# NIXIE_Mainboard.net
KiCad netlist of a schematic drawn in Altium Designer
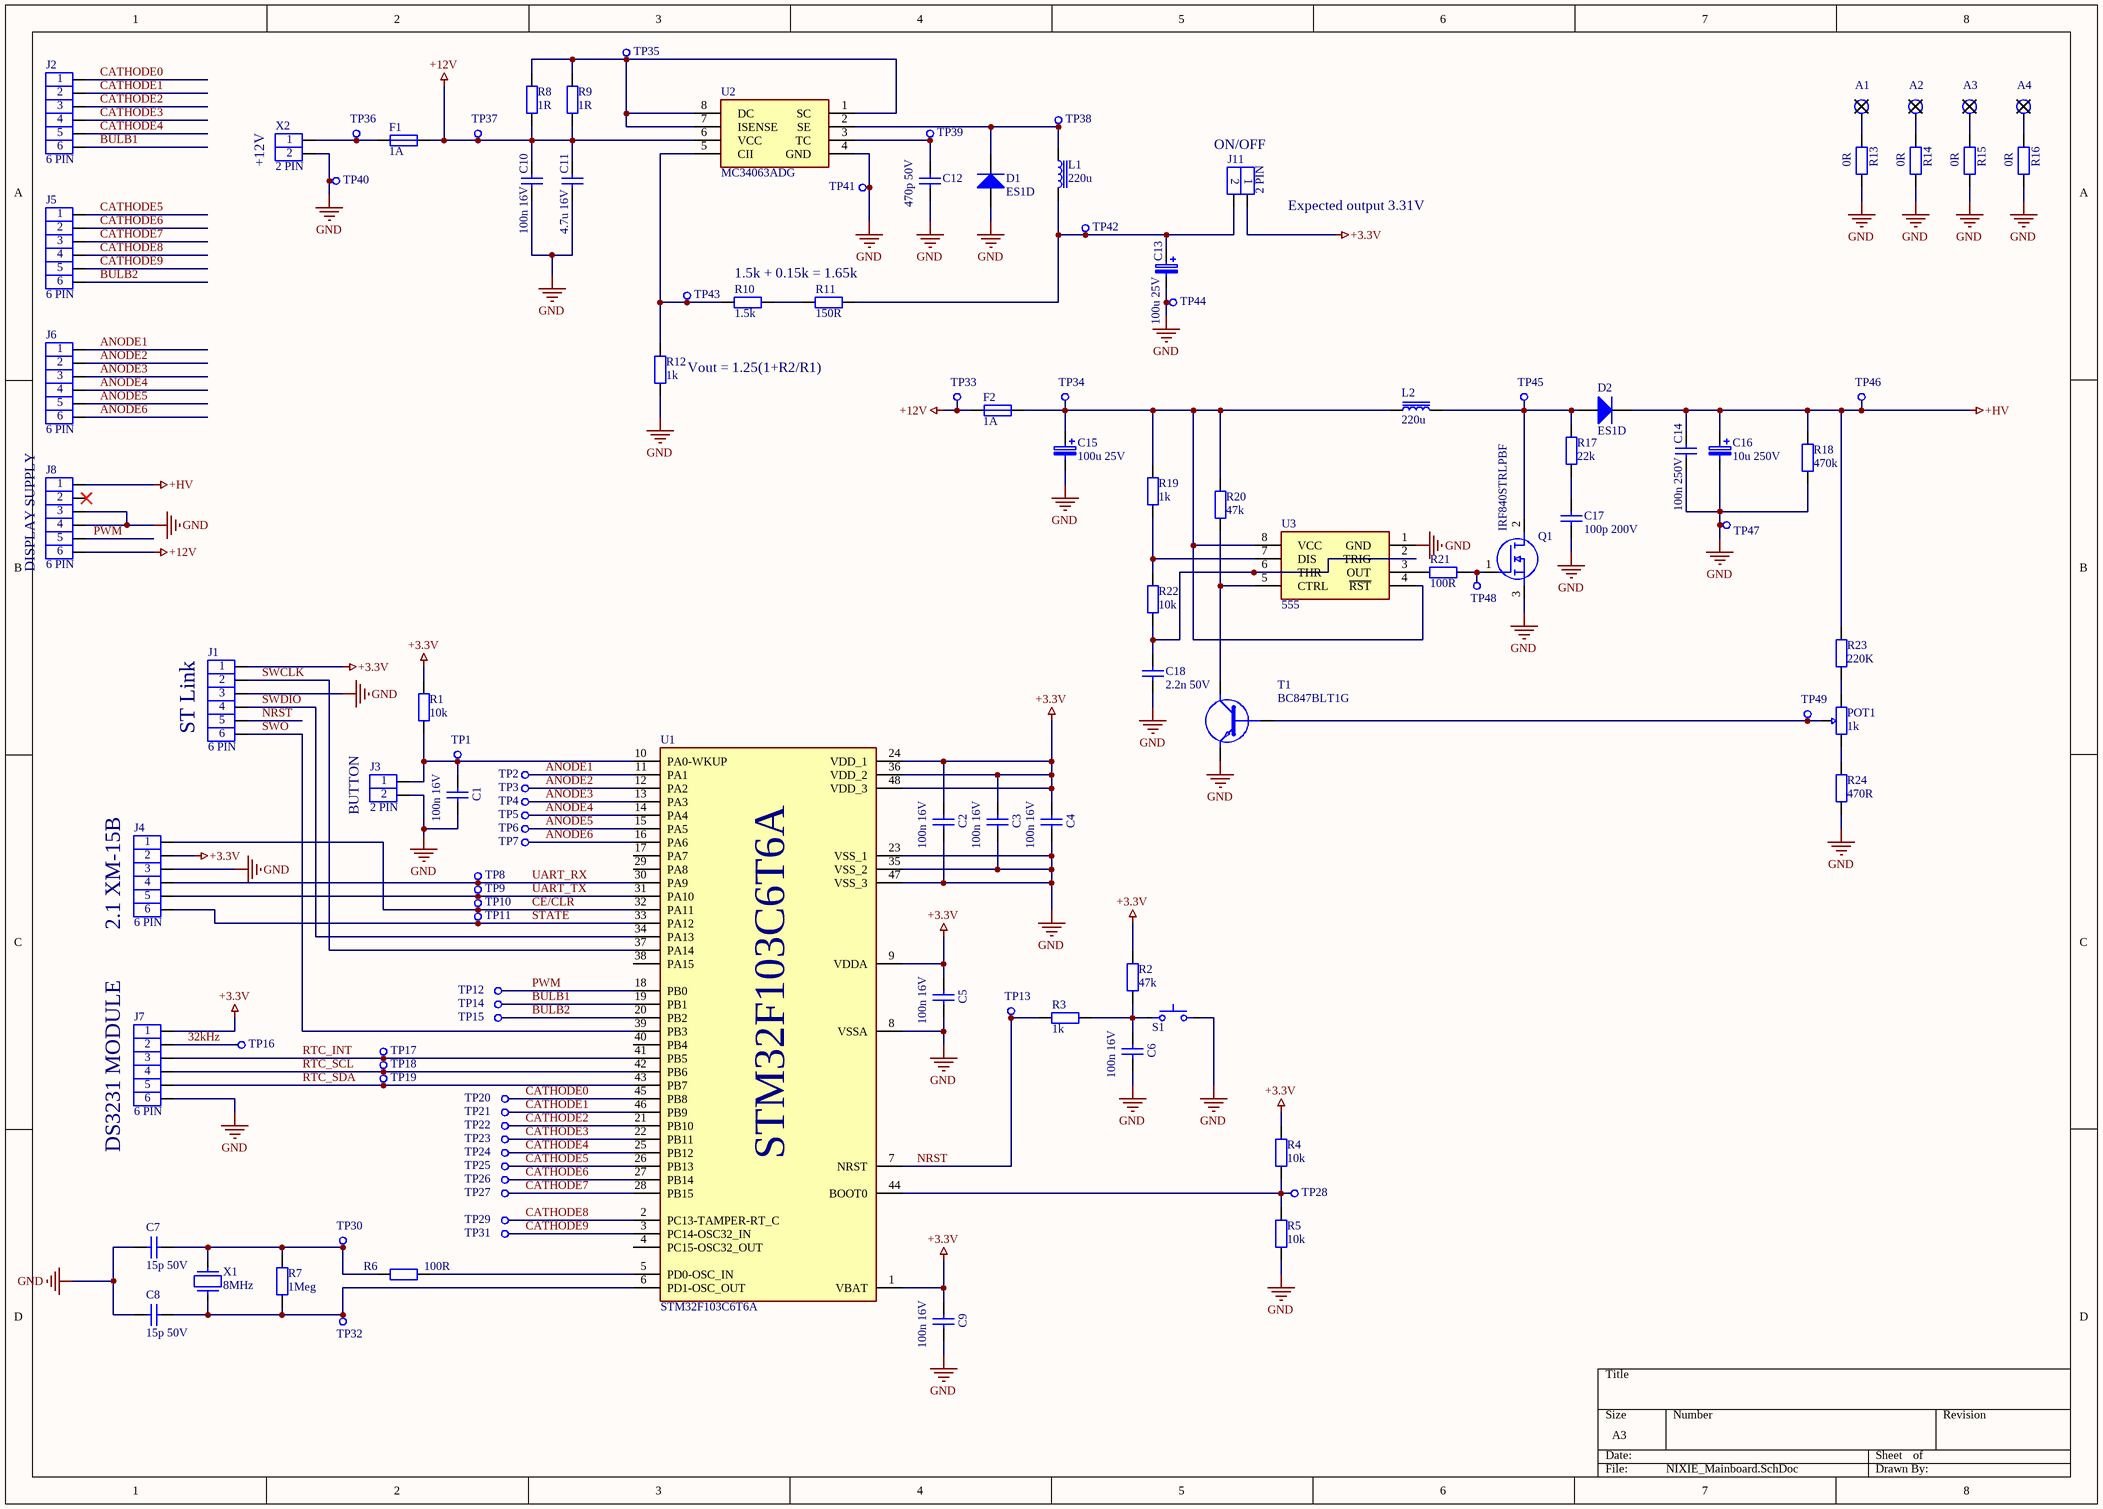
[diagram p0: NIXIE_Mainboard.SchDoc]

(export (version "E")
  (design (tool "Eeschema 10.0.6"))
  (components
    (comp (ref "A1")
      (value "3mm")
      (footprint "FOOTPRINTS:HOLE M3")
      (description "Mechanical M3 Hole")
      (libsource (lib "SYMBOLS") (part "Mechanical M3 Hole"))
    )
    (comp (ref "A2")
      (value "3mm")
      (footprint "FOOTPRINTS:HOLE M3")
      (description "Mechanical M3 Hole")
      (libsource (lib "SYMBOLS") (part "Mechanical M3 Hole"))
    )
    (comp (ref "A3")
      (value "3mm")
      (footprint "FOOTPRINTS:HOLE M3")
      (description "Mechanical M3 Hole")
      (libsource (lib "SYMBOLS") (part "Mechanical M3 Hole"))
    )
    (comp (ref "A4")
      (value "3mm")
      (footprint "FOOTPRINTS:HOLE M3")
      (description "Mechanical M3 Hole")
      (libsource (lib "SYMBOLS") (part "Mechanical M3 Hole"))
    )
    (comp (ref "C1")
      (value "100n 16V")
      (footprint "FOOTPRINTS:CAPACITOR 0603")
      (description "Multilayer Ceramic Capacitors MLCC - SMD/SMT 0603 16VDC 0.1uF 10% X7R")
      (fields
        (field (name "MANUFACTURER") "Taiyo Yuden")
        (field (name "MANUFACTURER PART NUMBER") "EMK107B7104KA-T")
      )
      (libsource (lib "SYMBOLS") (part "Capacitor 100n 16V 10% X7R 0603"))
    )
    (comp (ref "C2")
      (value "100n 16V")
      (footprint "FOOTPRINTS:CAPACITOR 0603")
      (description "Multilayer Ceramic Capacitors MLCC - SMD/SMT 0603 16VDC 0.1uF 10% X7R")
      (fields
        (field (name "MANUFACTURER") "Taiyo Yuden")
        (field (name "MANUFACTURER PART NUMBER") "EMK107B7104KA-T")
      )
      (libsource (lib "SYMBOLS") (part "Capacitor 100n 16V 10% X7R 0603"))
    )
    (comp (ref "C3")
      (value "100n 16V")
      (footprint "FOOTPRINTS:CAPACITOR 0603")
      (description "Multilayer Ceramic Capacitors MLCC - SMD/SMT 0603 16VDC 0.1uF 10% X7R")
      (fields
        (field (name "MANUFACTURER") "Taiyo Yuden")
        (field (name "MANUFACTURER PART NUMBER") "EMK107B7104KA-T")
      )
      (libsource (lib "SYMBOLS") (part "Capacitor 100n 16V 10% X7R 0603"))
    )
    (comp (ref "C4")
      (value "100n 16V")
      (footprint "FOOTPRINTS:CAPACITOR 0603")
      (description "Multilayer Ceramic Capacitors MLCC - SMD/SMT 0603 16VDC 0.1uF 10% X7R")
      (fields
        (field (name "MANUFACTURER") "Taiyo Yuden")
        (field (name "MANUFACTURER PART NUMBER") "EMK107B7104KA-T")
      )
      (libsource (lib "SYMBOLS") (part "Capacitor 100n 16V 10% X7R 0603"))
    )
    (comp (ref "C5")
      (value "100n 16V")
      (footprint "FOOTPRINTS:CAPACITOR 0603")
      (description "Multilayer Ceramic Capacitors MLCC - SMD/SMT 0603 16VDC 0.1uF 10% X7R")
      (fields
        (field (name "MANUFACTURER") "Taiyo Yuden")
        (field (name "MANUFACTURER PART NUMBER") "EMK107B7104KA-T")
      )
      (libsource (lib "SYMBOLS") (part "Capacitor 100n 16V 10% X7R 0603"))
    )
    (comp (ref "C6")
      (value "100n 16V")
      (footprint "FOOTPRINTS:CAPACITOR 0603")
      (description "Multilayer Ceramic Capacitors MLCC - SMD/SMT 0603 16VDC 0.1uF 10% X7R")
      (fields
        (field (name "MANUFACTURER") "Taiyo Yuden")
        (field (name "MANUFACTURER PART NUMBER") "EMK107B7104KA-T")
      )
      (libsource (lib "SYMBOLS") (part "Capacitor 100n 16V 10% X7R 0603"))
    )
    (comp (ref "C7")
      (value "15p 50V")
      (footprint "FOOTPRINTS:CAPACITOR 0603")
      (description "Multilayer Ceramic Capacitors MLCC - SMD/SMT 50 V 15 pF C0G 0603 5%")
      (fields
        (field (name "MANUFACTURER") "YAGEO")
        (field (name "MANUFACTURER PART NUMBER") "CC0603JPNPO9BN150")
      )
      (libsource (lib "SYMBOLS") (part "Capacitor 15p 50V 10% X7R 0603"))
    )
    (comp (ref "C8")
      (value "15p 50V")
      (footprint "FOOTPRINTS:CAPACITOR 0603")
      (description "Multilayer Ceramic Capacitors MLCC - SMD/SMT 50 V 15 pF C0G 0603 5%")
      (fields
        (field (name "MANUFACTURER") "YAGEO")
        (field (name "MANUFACTURER PART NUMBER") "CC0603JPNPO9BN150")
      )
      (libsource (lib "SYMBOLS") (part "Capacitor 15p 50V 10% X7R 0603"))
    )
    (comp (ref "C9")
      (value "100n 16V")
      (footprint "FOOTPRINTS:CAPACITOR 0603")
      (description "Multilayer Ceramic Capacitors MLCC - SMD/SMT 0603 16VDC 0.1uF 10% X7R")
      (fields
        (field (name "MANUFACTURER") "Taiyo Yuden")
        (field (name "MANUFACTURER PART NUMBER") "EMK107B7104KA-T")
      )
      (libsource (lib "SYMBOLS") (part "Capacitor 100n 16V 10% X7R 0603"))
    )
    (comp (ref "C10")
      (value "100n 16V")
      (footprint "FOOTPRINTS:CAPACITOR 0603")
      (description "Multilayer Ceramic Capacitors MLCC - SMD/SMT 0603 16VDC 0.1uF 10% X7R")
      (fields
        (field (name "MANUFACTURER") "Taiyo Yuden")
        (field (name "MANUFACTURER PART NUMBER") "EMK107B7104KA-T")
      )
      (libsource (lib "SYMBOLS") (part "Capacitor 100n 16V 10% X7R 0603"))
    )
    (comp (ref "C11")
      (value "4.7u 16V")
      (footprint "FOOTPRINTS:CAPACITOR 0805")
      (description "Multilayer Ceramic Capacitors MLCC - SMD/SMT 0805 16VDC 4.7uF 10% X7R")
      (fields
        (field (name "MANUFACTURER") "Taiyo Yuden")
        (field (name "MANUFACTURER PART NUMBER") "EMK212B7475KG-T")
      )
      (libsource (lib "SYMBOLS") (part "Capacitor 4.7u 16V 10% X7R 0805"))
    )
    (comp (ref "C12")
      (value "470p 50V")
      (footprint "FOOTPRINTS:CAPACITOR 0603")
      (description "Multilayer Ceramic Capacitors MLCC - SMD/SMT 470p +-10% 16VX7R")
      (fields
        (field (name "MANUFACTURER") "Walsin")
        (field (name "MANUFACTURER PART NUMBER") "CC0603KPX7R9BB471")
      )
      (libsource (lib "SYMBOLS") (part "Capacitor 470p 50V 10% X7R 0603"))
    )
    (comp (ref "C13")
      (value "100u 25V")
      (footprint "FOOTPRINTS:CAPACITOR 6.3X11MM THT")
      (description "Aluminum Electrolytic Capacitors - Radial Leaded 25V 100uF 105C 6.3x11mm")
      (fields
        (field (name "MANUFACTURER") "Lelon")
        (field (name "MANUFACTURER PART NUMBER") "RGA101M1EBK-0611G")
      )
      (libsource (lib "SYMBOLS") (part "Capacitor 100u 25V 20% Aluminum 6.3x11mm THT"))
    )
    (comp (ref "C14")
      (value "100n 250V")
      (footprint "FOOTPRINTS:CAPACITOR 1206")
      (description "Multilayer Ceramic Capacitors MLCC - SMD/SMT 250V 1000pF X7R 1206 5% Flex Term")
      (fields
        (field (name "MANUFACTURER") "KEMET")
        (field (name "MANUFACTURER PART NUMBER") "C1206X102JARACTU")
      )
      (libsource (lib "SYMBOLS") (part "Capacitor 100n 250V 5% X7R 1206"))
    )
    (comp (ref "C15")
      (value "100u 25V")
      (footprint "FOOTPRINTS:CAPACITOR 6.3X11MM THT")
      (description "Aluminum Electrolytic Capacitors - Radial Leaded 25V 100uF 105C 6.3x11mm")
      (fields
        (field (name "MANUFACTURER") "Lelon")
        (field (name "MANUFACTURER PART NUMBER") "RGA101M1EBK-0611G")
      )
      (libsource (lib "SYMBOLS") (part "Capacitor 100u 25V 20% Aluminum 6.3x11mm THT"))
    )
    (comp (ref "C16")
      (value "10u 250V")
      (footprint "FOOTPRINTS:CAPACITOR 10X20MM THT")
      (description "Aluminum Electrolytic Capacitors - Radial Leaded 25V 100uF 105C 6.3x11mm")
      (fields
        (field (name "MANUFACTURER") "Producent")
        (field (name "MANUFACTURER PART NUMBER") "PJ2E100MNN1020")
      )
      (libsource (lib "SYMBOLS") (part "Capacitor 10u 250V 20% Aluminum 10x20mm THT"))
    )
    (comp (ref "C17")
      (value "100p 200V")
      (footprint "FOOTPRINTS:CAPACITOR 1206")
      (description "Multilayer Ceramic Capacitors MLCC - SMD/SMT 200V 100pF X7R 1206 10% AEC-Q200")
      (fields
        (field (name "MANUFACTURER") "KEMET")
        (field (name "MANUFACTURER PART NUMBER") "C1206C101K2RACAUTO")
      )
      (libsource (lib "SYMBOLS") (part "Capacitor 100p 200V 10% X7R 1206"))
    )
    (comp (ref "C18")
      (value "2.2n 50V")
      (footprint "FOOTPRINTS:CAPACITOR 0603")
      (description "Multilayer Ceramic Capacitors MLCC - SMD/SMT 0603 50VDC 2200pF 10% X7R AEC-Q200")
      (fields
        (field (name "MANUFACTURER") "Taiyo Yuden")
        (field (name "MANUFACTURER PART NUMBER") "UMK107B7222KAHT")
      )
      (libsource (lib "SYMBOLS") (part "Capacitor 2.2n 50V 10% X7R 0603"))
    )
    (comp (ref "D1")
      (value "ES1D")
      (footprint "FOOTPRINTS:DIODE DO-214AC")
      (description "Rectifiers 1.0a Rectifier UF Recovery")
      (fields (field (name "MANUFACTURER") "onsemi / Fairchild"))
      (libsource (lib "SYMBOLS") (part "Diode 200V 1.5W 1A Rectifier Vf 920mV ES1D"))
    )
    (comp (ref "D2")
      (value "ES1D")
      (footprint "FOOTPRINTS:DIODE DO-214AC")
      (description "Rectifiers 1.0a Rectifier UF Recovery")
      (fields (field (name "MANUFACTURER") "onsemi / Fairchild"))
      (libsource (lib "SYMBOLS") (part "Diode 200V 1.5W 1A Rectifier Vf 920mV ES1D"))
    )
    (comp (ref "F1")
      (value "1A")
      (footprint "FOOTPRINTS:FUSE 1206")
      (description "Surface Mount Fuses 1A 63V TIME DELAY")
      (fields
        (field (name "MANUFACTURER") "Bourns")
        (field (name "MANUFACTURER PART NUMBER") "SF-1206HI100M-2")
      )
      (libsource (lib "SYMBOLS") (part "Fuse 1A 1% 1/4W 1206"))
    )
    (comp (ref "F2")
      (value "1A")
      (footprint "FOOTPRINTS:FUSE 1206")
      (description "Surface Mount Fuses 1A 63V TIME DELAY")
      (fields
        (field (name "MANUFACTURER") "Bourns")
        (field (name "MANUFACTURER PART NUMBER") "SF-1206HI100M-2")
      )
      (libsource (lib "SYMBOLS") (part "Fuse 1A 1% 1/4W 1206"))
    )
    (comp (ref "J1")
      (value "6 PIN")
      (footprint "FOOTPRINTS:MECHANICAL PINHEADER 6P 2.54MM MALE")
      (description "Headers & Wire Housings 2.54MM CGRIDIII HDR 6P VERT SR SEL AU")
      (fields (field (name "MANUFACTURER") "Molex") (field (name "MANUFACTURER PART NUMBER") "90120-0766"))
      (libsource (lib "SYMBOLS") (part "Mechanical Pinheader Male 6pin P=2.54mm THT"))
    )
    (comp (ref "J2")
      (value "6 PIN")
      (footprint "FOOTPRINTS:MECHANICAL PINHEADER 6P 2.54MM MALE")
      (description "Headers & Wire Housings 2.54MM CGRIDIII HDR 6P VERT SR SEL AU")
      (fields (field (name "MANUFACTURER") "Molex") (field (name "MANUFACTURER PART NUMBER") "90120-0766"))
      (libsource (lib "SYMBOLS") (part "Mechanical Pinheader Male 6pin P=2.54mm THT"))
    )
    (comp (ref "J3")
      (value "2 PIN")
      (footprint "FOOTPRINTS:MECHANICAL PINHEADER 2P 2.54MM MALE")
      (description "Headers & Wire Housings 2.54MM CGRIDIII HDR 2P VERT SR SEL AU")
      (fields (field (name "MANUFACTURER") "Molex") (field (name "MANUFACTURER PART NUMBER") "90120-0762"))
      (libsource (lib "") (part "Mechanical Pinheader Male 2pin P=2.54mm THT_1"))
    )
    (comp (ref "J4")
      (value "6 PIN")
      (footprint "FOOTPRINTS:MECHANICAL PINHEADER 6P 2.54MM MALE")
      (description "Headers & Wire Housings 2.54MM CGRIDIII HDR 6P VERT SR SEL AU")
      (fields (field (name "MANUFACTURER") "Molex") (field (name "MANUFACTURER PART NUMBER") "90120-0766"))
      (libsource (lib "SYMBOLS") (part "Mechanical Pinheader Male 6pin P=2.54mm THT"))
    )
    (comp (ref "J5")
      (value "6 PIN")
      (footprint "FOOTPRINTS:MECHANICAL PINHEADER 6P 2.54MM MALE")
      (description "Headers & Wire Housings 2.54MM CGRIDIII HDR 6P VERT SR SEL AU")
      (fields (field (name "MANUFACTURER") "Molex") (field (name "MANUFACTURER PART NUMBER") "90120-0766"))
      (libsource (lib "SYMBOLS") (part "Mechanical Pinheader Male 6pin P=2.54mm THT"))
    )
    (comp (ref "J6")
      (value "6 PIN")
      (footprint "FOOTPRINTS:MECHANICAL PINHEADER 6P 2.54MM MALE")
      (description "Headers & Wire Housings 2.54MM CGRIDIII HDR 6P VERT SR SEL AU")
      (fields (field (name "MANUFACTURER") "Molex") (field (name "MANUFACTURER PART NUMBER") "90120-0766"))
      (libsource (lib "SYMBOLS") (part "Mechanical Pinheader Male 6pin P=2.54mm THT"))
    )
    (comp (ref "J7")
      (value "6 PIN")
      (footprint "FOOTPRINTS:MECHANICAL PINHEADER 6P 2.54MM MALE")
      (description "Headers & Wire Housings 2.54MM CGRIDIII HDR 6P VERT SR SEL AU")
      (fields (field (name "MANUFACTURER") "Molex") (field (name "MANUFACTURER PART NUMBER") "90120-0766"))
      (libsource (lib "SYMBOLS") (part "Mechanical Pinheader Male 6pin P=2.54mm THT"))
    )
    (comp (ref "J8")
      (value "6 PIN")
      (footprint "FOOTPRINTS:MECHANICAL PINHEADER 6P 2.54MM MALE")
      (description "Headers & Wire Housings 2.54MM CGRIDIII HDR 6P VERT SR SEL AU")
      (fields (field (name "MANUFACTURER") "Molex") (field (name "MANUFACTURER PART NUMBER") "90120-0766"))
      (libsource (lib "SYMBOLS") (part "Mechanical Pinheader Male 6pin P=2.54mm THT"))
    )
    (comp (ref "J11")
      (value "2 PIN")
      (footprint "FOOTPRINTS:MECHANICAL PINHEADER 2P 2.54MM MALE")
      (description "Headers & Wire Housings 2.54MM CGRIDIII HDR 2P VERT SR SEL AU")
      (fields (field (name "MANUFACTURER") "Molex") (field (name "MANUFACTURER PART NUMBER") "90120-0762"))
      (libsource (lib "SYMBOLS") (part "Mechanical Pinheader Male 2pin P=2.54mm THT"))
    )
    (comp (ref "L1")
      (value "220u")
      (footprint "FOOTPRINTS:INDUCTOR CDRH127")
      (description "Power Inductors - SMD 220uH 0.95A Dual wind inductor")
      (fields
        (field (name "MANUFACTURER") "Murata Power Solutions")
        (field (name "MANUFACTURER PART NUMBER") "49221C")
      )
      (libsource (lib "SYMBOLS") (part "Inductor 220uH 0.95A Shielded 49221C"))
    )
    (comp (ref "L2")
      (value "220u")
      (footprint "FOOTPRINTS:INDUCTOR CDRH127")
      (description "Power Inductors - SMD 220uH 0.95A Dual wind inductor")
      (fields
        (field (name "MANUFACTURER") "Murata Power Solutions")
        (field (name "MANUFACTURER PART NUMBER") "49221C")
      )
      (libsource (lib "") (part "Inductor 220uH 0.95A Shielded 49221C_1"))
    )
    (comp (ref "POT1")
      (value "1k")
      (footprint "FOOTPRINTS:POTENTIOMETER TC33X")
      (description "Trimmer Resistors - SMD TRIMMER-3MM OPEN FRAME")
      (fields (field (name "MANUFACTURER") "Bourns") (field (name "MANUFACTURER PART NUMBER") "TC33X-1-102E"))
      (libsource (lib "SYMBOLS") (part "Potentiometer PCB 1k SMD TC33X-1-102E"))
    )
    (comp (ref "Q1")
      (value "IRF840STRLPBF")
      (footprint "FOOTPRINTS:TO-263-3")
      (description "MOSFET 500V N-CH HEXFET D2-PA")
      (fields (field (name "MANUFACTURER") "Vishay Semiconductors"))
      (libsource (lib "SYMBOLS") (part "Transistor N-MOSFET 500V 8A TO-263-3 IRF840STRLPBF"))
    )
    (comp (ref "R1")
      (value "10k")
      (footprint "FOOTPRINTS:RESISTOR 0603")
      (description "Thin Film Resistors - SMD 1/10W 10K ohm 1% 50ppm")
      (fields
        (field (name "MANUFACTURER") "Yageo")
        (field (name "MANUFACTURER PART NUMBER") "RT0603FRE1310KL")
      )
      (libsource (lib "SYMBOLS") (part "Resistor 10k 1% 1/10W 0603"))
    )
    (comp (ref "R2")
      (value "47k")
      (footprint "FOOTPRINTS:RESISTOR 0603")
      (description "Thin Film Resistors - SMD 1/10W 47K ohm 1% 50ppm")
      (fields
        (field (name "MANUFACTURER") "Yageo")
        (field (name "MANUFACTURER PART NUMBER") "RT0603FRE1347KL")
      )
      (libsource (lib "SYMBOLS") (part "Resistor 47k 1% 1/10W 0603"))
    )
    (comp (ref "R3")
      (value "1k")
      (footprint "FOOTPRINTS:RESISTOR 0603")
      (description "Thin Film Resistors - SMD 1/10W 1K ohm 1% 50ppm")
      (fields
        (field (name "MANUFACTURER") "Yageo")
        (field (name "MANUFACTURER PART NUMBER") "RT0603FRE071KL")
      )
      (libsource (lib "SYMBOLS") (part "Resistor 1k 1% 1/10W 0603"))
    )
    (comp (ref "R4")
      (value "10k")
      (footprint "FOOTPRINTS:RESISTOR 0603")
      (description "Thin Film Resistors - SMD 1/10W 10K ohm 1% 50ppm")
      (fields
        (field (name "MANUFACTURER") "Yageo")
        (field (name "MANUFACTURER PART NUMBER") "RT0603FRE1310KL")
      )
      (libsource (lib "SYMBOLS") (part "Resistor 10k 1% 1/10W 0603"))
    )
    (comp (ref "R5")
      (value "10k")
      (footprint "FOOTPRINTS:RESISTOR 0603")
      (description "Thin Film Resistors - SMD 1/10W 10K ohm 1% 50ppm")
      (fields
        (field (name "MANUFACTURER") "Yageo")
        (field (name "MANUFACTURER PART NUMBER") "RT0603FRE1310KL")
      )
      (libsource (lib "SYMBOLS") (part "Resistor 10k 1% 1/10W 0603"))
    )
    (comp (ref "R6")
      (value "100R")
      (footprint "FOOTPRINTS:RESISTOR 0603")
      (description "Thin Film Resistors - SMD 1/10W 100R ohm 1% 50ppm")
      (fields
        (field (name "MANUFACTURER") "Yageo")
        (field (name "MANUFACTURER PART NUMBER") "RT0603FRE07100RL")
      )
      (libsource (lib "SYMBOLS") (part "Resistor 100R 1% 1/10W 0603"))
    )
    (comp (ref "R7")
      (value "1Meg")
      (footprint "FOOTPRINTS:RESISTOR 0603")
      (description "Thin Film Resistors - SMD 1/10W 1M ohm 1% 50ppm")
      (fields
        (field (name "MANUFACTURER") "Yageo")
        (field (name "MANUFACTURER PART NUMBER") "RT0603FRE071ML")
      )
      (libsource (lib "SYMBOLS") (part "Resistor 1Meg 1% 1/10W 0603"))
    )
    (comp (ref "R8")
      (value "1R")
      (footprint "FOOTPRINTS:RESISTOR 1206")
      (description "Thick Film Resistors - SMD 1 Ohms 250 mW 1206 1%")
      (fields
        (field (name "MANUFACTURER") "Yageo")
        (field (name "MANUFACTURER PART NUMBER") "RC1206FR-071RL")
      )
      (libsource (lib "SYMBOLS") (part "Resistor 1R 1% 1/4W 1206"))
    )
    (comp (ref "R9")
      (value "1R")
      (footprint "FOOTPRINTS:RESISTOR 1206")
      (description "Thick Film Resistors - SMD 1 Ohms 250 mW 1206 1%")
      (fields
        (field (name "MANUFACTURER") "Yageo")
        (field (name "MANUFACTURER PART NUMBER") "RC1206FR-071RL")
      )
      (libsource (lib "SYMBOLS") (part "Resistor 1R 1% 1/4W 1206"))
    )
    (comp (ref "R10")
      (value "1.5k")
      (footprint "FOOTPRINTS:RESISTOR 0603")
      (description "Thin Film Resistors - SMD 1/10W 1.5K ohm 1% 50ppm")
      (fields
        (field (name "MANUFACTURER") "Yageo")
        (field (name "MANUFACTURER PART NUMBER") "RT0603FRE071K5L")
      )
      (libsource (lib "SYMBOLS") (part "Resistor 1.5k 1% 1/10W 0603"))
    )
    (comp (ref "R11")
      (value "150R")
      (footprint "FOOTPRINTS:RESISTOR 0603")
      (description "Thin Film Resistors - SMD 1/10W 150R ohm 1% 50ppm")
      (fields
        (field (name "MANUFACTURER") "Yageo")
        (field (name "MANUFACTURER PART NUMBER") "RT0603FRE07150RL")
      )
      (libsource (lib "SYMBOLS") (part "Resistor 150R 1% 1/10W 0603"))
    )
    (comp (ref "R12")
      (value "1k")
      (footprint "FOOTPRINTS:RESISTOR 0603")
      (description "Thin Film Resistors - SMD 1/10W 1K ohm 1% 50ppm")
      (fields
        (field (name "MANUFACTURER") "Yageo")
        (field (name "MANUFACTURER PART NUMBER") "RT0603FRE071KL")
      )
      (libsource (lib "") (part "Resistor 1k 1% 1/10W 0603_1"))
    )
    (comp (ref "R13")
      (value "0R")
      (footprint "FOOTPRINTS:RESISTOR 0603")
      (description "Thick Film Resistors - SMD 0 Ohms 100 mW 0603 5%")
      (fields
        (field (name "MANUFACTURER") "Yageo")
        (field (name "MANUFACTURER PART NUMBER") "RC0603JR-070RL")
      )
      (libsource (lib "SYMBOLS") (part "Resistor 0R 1% 1/10W 0603"))
    )
    (comp (ref "R14")
      (value "0R")
      (footprint "FOOTPRINTS:RESISTOR 0603")
      (description "Thick Film Resistors - SMD 0 Ohms 100 mW 0603 5%")
      (fields
        (field (name "MANUFACTURER") "Yageo")
        (field (name "MANUFACTURER PART NUMBER") "RC0603JR-070RL")
      )
      (libsource (lib "SYMBOLS") (part "Resistor 0R 1% 1/10W 0603"))
    )
    (comp (ref "R15")
      (value "0R")
      (footprint "FOOTPRINTS:RESISTOR 0603")
      (description "Thick Film Resistors - SMD 0 Ohms 100 mW 0603 5%")
      (fields
        (field (name "MANUFACTURER") "Yageo")
        (field (name "MANUFACTURER PART NUMBER") "RC0603JR-070RL")
      )
      (libsource (lib "SYMBOLS") (part "Resistor 0R 1% 1/10W 0603"))
    )
    (comp (ref "R16")
      (value "0R")
      (footprint "FOOTPRINTS:RESISTOR 0603")
      (description "Thick Film Resistors - SMD 0 Ohms 100 mW 0603 5%")
      (fields
        (field (name "MANUFACTURER") "Yageo")
        (field (name "MANUFACTURER PART NUMBER") "RC0603JR-070RL")
      )
      (libsource (lib "SYMBOLS") (part "Resistor 0R 1% 1/10W 0603"))
    )
    (comp (ref "R17")
      (value "22k")
      (footprint "FOOTPRINTS:RESISTOR 1206")
      (description "Thin Film Resistors - SMD 1/4W 22 kohm 1% 50ppm")
      (fields
        (field (name "MANUFACTURER") "Yageo")
        (field (name "MANUFACTURER PART NUMBER") "RT1206FRE0722KL")
      )
      (libsource (lib "SYMBOLS") (part "Resistor 22k 1% 1/4W 1206"))
    )
    (comp (ref "R18")
      (value "470k")
      (footprint "FOOTPRINTS:RESISTOR 1206")
      (description "Thin Film Resistors - SMD 1/4W470 kohm 1% 50ppm")
      (fields
        (field (name "MANUFACTURER") "Yageo")
        (field (name "MANUFACTURER PART NUMBER") "RT1206FRE07470KL")
      )
      (libsource (lib "SYMBOLS") (part "Resistor 470k 1% 1/4W 1206"))
    )
    (comp (ref "R19")
      (value "1k")
      (footprint "FOOTPRINTS:RESISTOR 0603")
      (description "Thin Film Resistors - SMD 1/10W 1K ohm 1% 50ppm")
      (fields
        (field (name "MANUFACTURER") "Yageo")
        (field (name "MANUFACTURER PART NUMBER") "RT0603FRE071KL")
      )
      (libsource (lib "") (part "Resistor 1k 1% 1/10W 0603_1"))
    )
    (comp (ref "R20")
      (value "47k")
      (footprint "FOOTPRINTS:RESISTOR 0603")
      (description "Thin Film Resistors - SMD 1/10W 47K ohm 1% 50ppm")
      (fields
        (field (name "MANUFACTURER") "Yageo")
        (field (name "MANUFACTURER PART NUMBER") "RT0603FRE1347KL")
      )
      (libsource (lib "SYMBOLS") (part "Resistor 47k 1% 1/10W 0603"))
    )
    (comp (ref "R21")
      (value "100R")
      (footprint "FOOTPRINTS:RESISTOR 0603")
      (description "Thin Film Resistors - SMD 1/10W 100R ohm 1% 50ppm")
      (fields
        (field (name "MANUFACTURER") "Yageo")
        (field (name "MANUFACTURER PART NUMBER") "RT0603FRE07100RL")
      )
      (libsource (lib "SYMBOLS") (part "Resistor 100R 1% 1/10W 0603"))
    )
    (comp (ref "R22")
      (value "10k")
      (footprint "FOOTPRINTS:RESISTOR 0603")
      (description "Thin Film Resistors - SMD 1/10W 10K ohm 1% 50ppm")
      (fields
        (field (name "MANUFACTURER") "Yageo")
        (field (name "MANUFACTURER PART NUMBER") "RT0603FRE1310KL")
      )
      (libsource (lib "SYMBOLS") (part "Resistor 10k 1% 1/10W 0603"))
    )
    (comp (ref "R23")
      (value "220K")
      (footprint "FOOTPRINTS:RESISTOR 1206")
      (description "Thin Film Resistors - SMD 1/4W 220 kohm 1% 50ppm")
      (fields
        (field (name "MANUFACTURER") "Yageo")
        (field (name "MANUFACTURER PART NUMBER") "RT1206FRE07220KL")
      )
      (libsource (lib "SYMBOLS") (part "Resistor 220k 1% 1/4W 1206"))
    )
    (comp (ref "R24")
      (value "470R")
      (footprint "FOOTPRINTS:RESISTOR 0603")
      (description "Thin Film Resistors - SMD 1/10W 470R ohm 1% 50ppm")
      (fields
        (field (name "MANUFACTURER") "Yageo")
        (field (name "MANUFACTURER PART NUMBER") "RT0603FRE07470RL")
      )
      (libsource (lib "SYMBOLS") (part "Resistor 470R 1% 1/10W 0603"))
    )
    (comp (ref "S1")
      (value "6x6mm")
      (footprint "FOOTPRINTS:MECHANICAL TACTSWITCH SMD 6x6")
      (description "Tactile Switches 6 x 6 mm, 5 mm Act Height, 260 gf, Black, Short Crimped, Through Hole, SPST")
      (fields
        (field (name "MANUFACTURER") "CUI Devices")
        (field (name "MANUFACTURER PART NUMBER") "TS02-66-50-BK-260-SCR-D")
      )
      (libsource (lib "SYMBOLS") (part "Mechanical Tact Switch 6x6mm THT"))
    )
    (comp (ref "T1")
      (value "BC847BLT1G")
      (footprint "FOOTPRINTS:SOT23-3")
      (description "Bipolar Transistors - BJT 100mA 50V NPN")
      (fields (field (name "MANUFACTURER") "onsemi"))
      (libsource (lib "SYMBOLS") (part "Transistor NPN 100mA 50V BC847BLT1G"))
    )
    (comp (ref "TP1")
      (value "1mm")
      (footprint "FOOTPRINTS:TEST POINT 1MM")
      (description "Tesp Point 1mm")
      (libsource (lib "SYMBOLS") (part "Mechanical Test Point 1mm"))
    )
    (comp (ref "TP2")
      (value "1mm")
      (footprint "FOOTPRINTS:TEST POINT 1MM")
      (description "Tesp Point 1mm")
      (libsource (lib "SYMBOLS") (part "Mechanical Test Point 1mm"))
    )
    (comp (ref "TP3")
      (value "1mm")
      (footprint "FOOTPRINTS:TEST POINT 1MM")
      (description "Tesp Point 1mm")
      (libsource (lib "SYMBOLS") (part "Mechanical Test Point 1mm"))
    )
    (comp (ref "TP4")
      (value "1mm")
      (footprint "FOOTPRINTS:TEST POINT 1MM")
      (description "Tesp Point 1mm")
      (libsource (lib "SYMBOLS") (part "Mechanical Test Point 1mm"))
    )
    (comp (ref "TP5")
      (value "1mm")
      (footprint "FOOTPRINTS:TEST POINT 1MM")
      (description "Tesp Point 1mm")
      (libsource (lib "SYMBOLS") (part "Mechanical Test Point 1mm"))
    )
    (comp (ref "TP6")
      (value "1mm")
      (footprint "FOOTPRINTS:TEST POINT 1MM")
      (description "Tesp Point 1mm")
      (libsource (lib "SYMBOLS") (part "Mechanical Test Point 1mm"))
    )
    (comp (ref "TP7")
      (value "1mm")
      (footprint "FOOTPRINTS:TEST POINT 1MM")
      (description "Tesp Point 1mm")
      (libsource (lib "SYMBOLS") (part "Mechanical Test Point 1mm"))
    )
    (comp (ref "TP8")
      (value "1mm")
      (footprint "FOOTPRINTS:TEST POINT 1MM")
      (description "Tesp Point 1mm")
      (libsource (lib "SYMBOLS") (part "Mechanical Test Point 1mm"))
    )
    (comp (ref "TP9")
      (value "1mm")
      (footprint "FOOTPRINTS:TEST POINT 1MM")
      (description "Tesp Point 1mm")
      (libsource (lib "SYMBOLS") (part "Mechanical Test Point 1mm"))
    )
    (comp (ref "TP10")
      (value "1mm")
      (footprint "FOOTPRINTS:TEST POINT 1MM")
      (description "Tesp Point 1mm")
      (libsource (lib "SYMBOLS") (part "Mechanical Test Point 1mm"))
    )
    (comp (ref "TP11")
      (value "1mm")
      (footprint "FOOTPRINTS:TEST POINT 1MM")
      (description "Tesp Point 1mm")
      (libsource (lib "SYMBOLS") (part "Mechanical Test Point 1mm"))
    )
    (comp (ref "TP12")
      (value "1mm")
      (footprint "FOOTPRINTS:TEST POINT 1MM")
      (description "Tesp Point 1mm")
      (libsource (lib "SYMBOLS") (part "Mechanical Test Point 1mm"))
    )
    (comp (ref "TP13")
      (value "1mm")
      (footprint "FOOTPRINTS:TEST POINT 1MM")
      (description "Tesp Point 1mm")
      (libsource (lib "SYMBOLS") (part "Mechanical Test Point 1mm"))
    )
    (comp (ref "TP14")
      (value "1mm")
      (footprint "FOOTPRINTS:TEST POINT 1MM")
      (description "Tesp Point 1mm")
      (libsource (lib "SYMBOLS") (part "Mechanical Test Point 1mm"))
    )
    (comp (ref "TP15")
      (value "1mm")
      (footprint "FOOTPRINTS:TEST POINT 1MM")
      (description "Tesp Point 1mm")
      (libsource (lib "SYMBOLS") (part "Mechanical Test Point 1mm"))
    )
    (comp (ref "TP16")
      (value "1mm")
      (footprint "FOOTPRINTS:TEST POINT 1MM")
      (description "Tesp Point 1mm")
      (libsource (lib "SYMBOLS") (part "Mechanical Test Point 1mm"))
    )
    (comp (ref "TP17")
      (value "1mm")
      (footprint "FOOTPRINTS:TEST POINT 1MM")
      (description "Tesp Point 1mm")
      (libsource (lib "SYMBOLS") (part "Mechanical Test Point 1mm"))
    )
    (comp (ref "TP18")
      (value "1mm")
      (footprint "FOOTPRINTS:TEST POINT 1MM")
      (description "Tesp Point 1mm")
      (libsource (lib "SYMBOLS") (part "Mechanical Test Point 1mm"))
    )
    (comp (ref "TP19")
      (value "1mm")
      (footprint "FOOTPRINTS:TEST POINT 1MM")
      (description "Tesp Point 1mm")
      (libsource (lib "SYMBOLS") (part "Mechanical Test Point 1mm"))
    )
    (comp (ref "TP20")
      (value "1mm")
      (footprint "FOOTPRINTS:TEST POINT 1MM")
      (description "Tesp Point 1mm")
      (libsource (lib "SYMBOLS") (part "Mechanical Test Point 1mm"))
    )
    (comp (ref "TP21")
      (value "1mm")
      (footprint "FOOTPRINTS:TEST POINT 1MM")
      (description "Tesp Point 1mm")
      (libsource (lib "SYMBOLS") (part "Mechanical Test Point 1mm"))
    )
    (comp (ref "TP22")
      (value "1mm")
      (footprint "FOOTPRINTS:TEST POINT 1MM")
      (description "Tesp Point 1mm")
      (libsource (lib "SYMBOLS") (part "Mechanical Test Point 1mm"))
    )
    (comp (ref "TP23")
      (value "1mm")
      (footprint "FOOTPRINTS:TEST POINT 1MM")
      (description "Tesp Point 1mm")
      (libsource (lib "SYMBOLS") (part "Mechanical Test Point 1mm"))
    )
    (comp (ref "TP24")
      (value "1mm")
      (footprint "FOOTPRINTS:TEST POINT 1MM")
      (description "Tesp Point 1mm")
      (libsource (lib "SYMBOLS") (part "Mechanical Test Point 1mm"))
    )
    (comp (ref "TP25")
      (value "1mm")
      (footprint "FOOTPRINTS:TEST POINT 1MM")
      (description "Tesp Point 1mm")
      (libsource (lib "SYMBOLS") (part "Mechanical Test Point 1mm"))
    )
    (comp (ref "TP26")
      (value "1mm")
      (footprint "FOOTPRINTS:TEST POINT 1MM")
      (description "Tesp Point 1mm")
      (libsource (lib "SYMBOLS") (part "Mechanical Test Point 1mm"))
    )
    (comp (ref "TP27")
      (value "1mm")
      (footprint "FOOTPRINTS:TEST POINT 1MM")
      (description "Tesp Point 1mm")
      (libsource (lib "SYMBOLS") (part "Mechanical Test Point 1mm"))
    )
    (comp (ref "TP28")
      (value "1mm")
      (footprint "FOOTPRINTS:TEST POINT 1MM")
      (description "Tesp Point 1mm")
      (libsource (lib "SYMBOLS") (part "Mechanical Test Point 1mm"))
    )
    (comp (ref "TP29")
      (value "1mm")
      (footprint "FOOTPRINTS:TEST POINT 1MM")
      (description "Tesp Point 1mm")
      (libsource (lib "SYMBOLS") (part "Mechanical Test Point 1mm"))
    )
    (comp (ref "TP30")
      (value "1mm")
      (footprint "FOOTPRINTS:TEST POINT 1MM")
      (description "Tesp Point 1mm")
      (libsource (lib "SYMBOLS") (part "Mechanical Test Point 1mm"))
    )
    (comp (ref "TP31")
      (value "1mm")
      (footprint "FOOTPRINTS:TEST POINT 1MM")
      (description "Tesp Point 1mm")
      (libsource (lib "SYMBOLS") (part "Mechanical Test Point 1mm"))
    )
    (comp (ref "TP32")
      (value "1mm")
      (footprint "FOOTPRINTS:TEST POINT 1MM")
      (description "Tesp Point 1mm")
      (libsource (lib "SYMBOLS") (part "Mechanical Test Point 1mm"))
    )
    (comp (ref "TP33")
      (value "1mm")
      (footprint "FOOTPRINTS:TEST POINT 1MM")
      (description "Tesp Point 1mm")
      (libsource (lib "SYMBOLS") (part "Mechanical Test Point 1mm"))
    )
    (comp (ref "TP34")
      (value "1mm")
      (footprint "FOOTPRINTS:TEST POINT 1MM")
      (description "Tesp Point 1mm")
      (libsource (lib "SYMBOLS") (part "Mechanical Test Point 1mm"))
    )
    (comp (ref "TP35")
      (value "1mm")
      (footprint "FOOTPRINTS:TEST POINT 1MM")
      (description "Tesp Point 1mm")
      (libsource (lib "SYMBOLS") (part "Mechanical Test Point 1mm"))
    )
    (comp (ref "TP36")
      (value "1mm")
      (footprint "FOOTPRINTS:TEST POINT 1MM")
      (description "Tesp Point 1mm")
      (libsource (lib "SYMBOLS") (part "Mechanical Test Point 1mm"))
    )
    (comp (ref "TP37")
      (value "1mm")
      (footprint "FOOTPRINTS:TEST POINT 1MM")
      (description "Tesp Point 1mm")
      (libsource (lib "SYMBOLS") (part "Mechanical Test Point 1mm"))
    )
    (comp (ref "TP38")
      (value "1mm")
      (footprint "FOOTPRINTS:TEST POINT 1MM")
      (description "Tesp Point 1mm")
      (libsource (lib "SYMBOLS") (part "Mechanical Test Point 1mm"))
    )
    (comp (ref "TP39")
      (value "1mm")
      (footprint "FOOTPRINTS:TEST POINT 1MM")
      (description "Tesp Point 1mm")
      (libsource (lib "SYMBOLS") (part "Mechanical Test Point 1mm"))
    )
    (comp (ref "TP40")
      (value "1mm")
      (footprint "FOOTPRINTS:TEST POINT 1MM")
      (description "Tesp Point 1mm")
      (libsource (lib "SYMBOLS") (part "Mechanical Test Point 1mm"))
    )
    (comp (ref "TP41")
      (value "1mm")
      (footprint "FOOTPRINTS:TEST POINT 1MM")
      (description "Tesp Point 1mm")
      (libsource (lib "SYMBOLS") (part "Mechanical Test Point 1mm"))
    )
    (comp (ref "TP42")
      (value "1mm")
      (footprint "FOOTPRINTS:TEST POINT 1MM")
      (description "Tesp Point 1mm")
      (libsource (lib "SYMBOLS") (part "Mechanical Test Point 1mm"))
    )
    (comp (ref "TP43")
      (value "1mm")
      (footprint "FOOTPRINTS:TEST POINT 1MM")
      (description "Tesp Point 1mm")
      (libsource (lib "SYMBOLS") (part "Mechanical Test Point 1mm"))
    )
    (comp (ref "TP44")
      (value "1mm")
      (footprint "FOOTPRINTS:TEST POINT 1MM")
      (description "Tesp Point 1mm")
      (libsource (lib "SYMBOLS") (part "Mechanical Test Point 1mm"))
    )
    (comp (ref "TP45")
      (value "1mm")
      (footprint "FOOTPRINTS:TEST POINT 1MM")
      (description "Tesp Point 1mm")
      (libsource (lib "SYMBOLS") (part "Mechanical Test Point 1mm"))
    )
    (comp (ref "TP46")
      (value "1mm")
      (footprint "FOOTPRINTS:TEST POINT 1MM")
      (description "Tesp Point 1mm")
      (libsource (lib "SYMBOLS") (part "Mechanical Test Point 1mm"))
    )
    (comp (ref "TP47")
      (value "1mm")
      (footprint "FOOTPRINTS:TEST POINT 1MM")
      (description "Tesp Point 1mm")
      (libsource (lib "SYMBOLS") (part "Mechanical Test Point 1mm"))
    )
    (comp (ref "TP48")
      (value "1mm")
      (footprint "FOOTPRINTS:TEST POINT 1MM")
      (description "Tesp Point 1mm")
      (libsource (lib "SYMBOLS") (part "Mechanical Test Point 1mm"))
    )
    (comp (ref "TP49")
      (value "1mm")
      (footprint "FOOTPRINTS:TEST POINT 1MM")
      (description "Tesp Point 1mm")
      (libsource (lib "SYMBOLS") (part "Mechanical Test Point 1mm"))
    )
    (comp (ref "U1")
      (value "STM32F103C6T6A")
      (footprint "FOOTPRINTS:LQFP-48")
      (description "ARM Microcontrollers - MCU 32BIT Cortex M3 L/D Performance LINE")
      (fields (field (name "MANUFACTURER") "STMicroelectronics"))
      (libsource (lib "SYMBOLS") (part "IC MCU ARM M3 STM32F103C6T6A"))
    )
    (comp (ref "U2")
      (value "MC34063ADG")
      (footprint "FOOTPRINTS:SOIC-8")
      (description "LDO Voltage Regulators 45V Vin, 100mA, Low Noise, Low Dropout, Micropower Linear Regulator")
      (fields (field (name "MANUFACTURER") "onsemi"))
      (libsource (lib "SYMBOLS") (part "IC Switching Voltage Regulator SOIC-8 40V 1.5A MC34063ADG"))
    )
    (comp (ref "U3")
      (value "555")
      (footprint "FOOTPRINTS:SOIC-8")
      (description "Timers & Support Products Precision")
      (fields
        (field (name "MANUFACTURER") "Texas Instruments")
        (field (name "MANUFACTURER PART NUMBER") "NE555DR")
      )
      (libsource (lib "SYMBOLS") (part "IC Timer Module 555 SO-8"))
    )
    (comp (ref "X1")
      (value "8MHz")
      (footprint "FOOTPRINTS:OSCILLATOR 8MHZ SMD")
      (description "Crystals CRYSTAL 8.0000MHZ 20PF SMD")
      (fields
        (field (name "MANUFACTURER") "ABRACON")
        (field (name "MANUFACTURER PART NUMBER") "ABLS-8.000MHZ-20-B-3-H-T")
      )
      (libsource (lib "SYMBOLS") (part "Crystal 8MHz 20p SMD"))
    )
    (comp (ref "X2")
      (value "2 PIN")
      (footprint "FOOTPRINTS:MECHANICAL ARK KF301 2PIN")
      (fields
        (field (name "MANUFACTURER") "CUI Devices")
        (field (name "MANUFACTURER PART NUMBER") "TB003-500-P02BE")
      )
      (libsource (lib "SYMBOLS") (part "Mechanical ARK Terminal Block 2pin P=5mm THT"))
    )
  )
  (nets
    (net (code "1") (name "+3.3V") (class "Default")
      (node (ref "C2") (pin "2") (pinfunction "2_2") (pintype "passive"))
      (node (ref "C3") (pin "2") (pinfunction "2_2") (pintype "passive"))
      (node (ref "C4") (pin "2") (pinfunction "2_2") (pintype "passive"))
      (node (ref "C5") (pin "2") (pinfunction "2_2") (pintype "passive"))
      (node (ref "C9") (pin "2") (pinfunction "2_2") (pintype "passive"))
      (node (ref "J1") (pin "1") (pinfunction "1_1") (pintype "passive"))
      (node (ref "J11") (pin "1") (pinfunction "1_1") (pintype "passive"))
      (node (ref "J4") (pin "2") (pinfunction "2_2") (pintype "passive"))
      (node (ref "J7") (pin "1") (pinfunction "1_1") (pintype "passive"))
      (node (ref "R1") (pin "2") (pinfunction "2_2") (pintype "passive"))
      (node (ref "R2") (pin "2") (pinfunction "2_2") (pintype "passive"))
      (node (ref "R4") (pin "2") (pinfunction "2_2") (pintype "passive"))
      (node (ref "U1") (pin "1") (pinfunction "VBAT_1") (pintype "passive"))
      (node (ref "U1") (pin "24") (pinfunction "VDD_1_24") (pintype "passive"))
      (node (ref "U1") (pin "36") (pinfunction "VDD_2_36") (pintype "passive"))
      (node (ref "U1") (pin "48") (pinfunction "VDD_3_48") (pintype "passive"))
      (node (ref "U1") (pin "9") (pinfunction "VDDA_9") (pintype "passive"))
    )
    (net (code "2") (name "+12V") (class "Default")
      (node (ref "C10") (pin "2") (pinfunction "2_2") (pintype "passive"))
      (node (ref "C11") (pin "2") (pinfunction "2_2") (pintype "passive"))
      (node (ref "F1") (pin "2") (pinfunction "2_2") (pintype "passive"))
      (node (ref "F2") (pin "1") (pinfunction "1_1") (pintype "passive"))
      (node (ref "J8") (pin "6") (pinfunction "6_6") (pintype "passive"))
      (node (ref "R8") (pin "1") (pinfunction "1_1") (pintype "passive"))
      (node (ref "R9") (pin "1") (pinfunction "1_1") (pintype "passive"))
      (node (ref "TP33") (pin "1") (pinfunction "1_1") (pintype "passive"))
      (node (ref "TP37") (pin "1") (pinfunction "1_1") (pintype "passive"))
      (node (ref "U2") (pin "6") (pinfunction "VCC_6") (pintype "passive"))
    )
    (net (code "3") (name "+HV") (class "Default")
      (node (ref "C14") (pin "2") (pinfunction "2_2") (pintype "passive"))
      (node (ref "C16") (pin "1") (pinfunction "1_1") (pintype "passive"))
      (node (ref "D2") (pin "2") (pinfunction "2_2") (pintype "passive"))
      (node (ref "J8") (pin "1") (pinfunction "1_1") (pintype "passive"))
      (node (ref "R18") (pin "2") (pinfunction "2_2") (pintype "passive"))
      (node (ref "R23") (pin "2") (pinfunction "2_2") (pintype "passive"))
      (node (ref "TP46") (pin "1") (pinfunction "1_1") (pintype "passive"))
    )
    (net (code "4") (name "/32kHz") (class "Default")
      (node (ref "J7") (pin "2") (pinfunction "2_2") (pintype "passive"))
      (node (ref "TP16") (pin "1") (pinfunction "1_1") (pintype "passive"))
    )
    (net (code "5") (name "/ANODE1") (class "Default")
      (node (ref "J6") (pin "1") (pinfunction "1_1") (pintype "passive"))
      (node (ref "TP2") (pin "1") (pinfunction "1_1") (pintype "passive"))
      (node (ref "U1") (pin "11") (pinfunction "PA1_11") (pintype "passive"))
    )
    (net (code "6") (name "/ANODE2") (class "Default")
      (node (ref "J6") (pin "2") (pinfunction "2_2") (pintype "passive"))
      (node (ref "TP3") (pin "1") (pinfunction "1_1") (pintype "passive"))
      (node (ref "U1") (pin "12") (pinfunction "PA2_12") (pintype "passive"))
    )
    (net (code "7") (name "/ANODE3") (class "Default")
      (node (ref "J6") (pin "3") (pinfunction "3_3") (pintype "passive"))
      (node (ref "TP4") (pin "1") (pinfunction "1_1") (pintype "passive"))
      (node (ref "U1") (pin "13") (pinfunction "PA3_13") (pintype "passive"))
    )
    (net (code "8") (name "/ANODE4") (class "Default")
      (node (ref "J6") (pin "4") (pinfunction "4_4") (pintype "passive"))
      (node (ref "TP5") (pin "1") (pinfunction "1_1") (pintype "passive"))
      (node (ref "U1") (pin "14") (pinfunction "PA4_14") (pintype "passive"))
    )
    (net (code "9") (name "/ANODE5") (class "Default")
      (node (ref "J6") (pin "5") (pinfunction "5_5") (pintype "passive"))
      (node (ref "TP6") (pin "1") (pinfunction "1_1") (pintype "passive"))
      (node (ref "U1") (pin "15") (pinfunction "PA5_15") (pintype "passive"))
    )
    (net (code "10") (name "/ANODE6") (class "Default")
      (node (ref "J6") (pin "6") (pinfunction "6_6") (pintype "passive"))
      (node (ref "TP7") (pin "1") (pinfunction "1_1") (pintype "passive"))
      (node (ref "U1") (pin "16") (pinfunction "PA6_16") (pintype "passive"))
    )
    (net (code "11") (name "/BULB1") (class "Default")
      (node (ref "J2") (pin "6") (pinfunction "6_6") (pintype "passive"))
      (node (ref "TP14") (pin "1") (pinfunction "1_1") (pintype "passive"))
      (node (ref "U1") (pin "19") (pinfunction "PB1_19") (pintype "passive"))
    )
    (net (code "12") (name "/BULB2") (class "Default")
      (node (ref "J5") (pin "6") (pinfunction "6_6") (pintype "passive"))
      (node (ref "TP15") (pin "1") (pinfunction "1_1") (pintype "passive"))
      (node (ref "U1") (pin "20") (pinfunction "PB2_20") (pintype "passive"))
    )
    (net (code "13") (name "/CATHODE0") (class "Default")
      (node (ref "J2") (pin "1") (pinfunction "1_1") (pintype "passive"))
      (node (ref "TP20") (pin "1") (pinfunction "1_1") (pintype "passive"))
      (node (ref "U1") (pin "45") (pinfunction "PB8_45") (pintype "passive"))
    )
    (net (code "14") (name "/CATHODE1") (class "Default")
      (node (ref "J2") (pin "2") (pinfunction "2_2") (pintype "passive"))
      (node (ref "TP21") (pin "1") (pinfunction "1_1") (pintype "passive"))
      (node (ref "U1") (pin "46") (pinfunction "PB9_46") (pintype "passive"))
    )
    (net (code "15") (name "/CATHODE2") (class "Default")
      (node (ref "J2") (pin "3") (pinfunction "3_3") (pintype "passive"))
      (node (ref "TP22") (pin "1") (pinfunction "1_1") (pintype "passive"))
      (node (ref "U1") (pin "21") (pinfunction "PB10_21") (pintype "passive"))
    )
    (net (code "16") (name "/CATHODE3") (class "Default")
      (node (ref "J2") (pin "4") (pinfunction "4_4") (pintype "passive"))
      (node (ref "TP23") (pin "1") (pinfunction "1_1") (pintype "passive"))
      (node (ref "U1") (pin "22") (pinfunction "PB11_22") (pintype "passive"))
    )
    (net (code "17") (name "/CATHODE4") (class "Default")
      (node (ref "J2") (pin "5") (pinfunction "5_5") (pintype "passive"))
      (node (ref "TP24") (pin "1") (pinfunction "1_1") (pintype "passive"))
      (node (ref "U1") (pin "25") (pinfunction "PB12_25") (pintype "passive"))
    )
    (net (code "18") (name "/CATHODE5") (class "Default")
      (node (ref "J5") (pin "1") (pinfunction "1_1") (pintype "passive"))
      (node (ref "TP25") (pin "1") (pinfunction "1_1") (pintype "passive"))
      (node (ref "U1") (pin "26") (pinfunction "PB13_26") (pintype "passive"))
    )
    (net (code "19") (name "/CATHODE6") (class "Default")
      (node (ref "J5") (pin "2") (pinfunction "2_2") (pintype "passive"))
      (node (ref "TP26") (pin "1") (pinfunction "1_1") (pintype "passive"))
      (node (ref "U1") (pin "27") (pinfunction "PB14_27") (pintype "passive"))
    )
    (net (code "20") (name "/CATHODE7") (class "Default")
      (node (ref "J5") (pin "3") (pinfunction "3_3") (pintype "passive"))
      (node (ref "TP27") (pin "1") (pinfunction "1_1") (pintype "passive"))
      (node (ref "U1") (pin "28") (pinfunction "PB15_28") (pintype "passive"))
    )
    (net (code "21") (name "/CATHODE8") (class "Default")
      (node (ref "J5") (pin "4") (pinfunction "4_4") (pintype "passive"))
      (node (ref "TP29") (pin "1") (pinfunction "1_1") (pintype "passive"))
      (node (ref "U1") (pin "2") (pinfunction "PC13-TAMPER-RT_C_2") (pintype "passive"))
    )
    (net (code "22") (name "/CATHODE9") (class "Default")
      (node (ref "J5") (pin "5") (pinfunction "5_5") (pintype "passive"))
      (node (ref "TP31") (pin "1") (pinfunction "1_1") (pintype "passive"))
      (node (ref "U1") (pin "3") (pinfunction "PC14-OSC32_IN_3") (pintype "passive"))
    )
    (net (code "23") (name "/CE{slash}CLR") (class "Default")
      (node (ref "J4") (pin "1") (pinfunction "1_1") (pintype "passive"))
      (node (ref "TP10") (pin "1") (pinfunction "1_1") (pintype "passive"))
      (node (ref "U1") (pin "32") (pinfunction "PA11_32") (pintype "passive"))
    )
    (net (code "24") (name "/NRST") (class "Default")
      (node (ref "J1") (pin "5") (pinfunction "5_5") (pintype "passive"))
      (node (ref "R3") (pin "2") (pinfunction "2_2") (pintype "passive"))
      (node (ref "TP13") (pin "1") (pinfunction "1_1") (pintype "passive"))
      (node (ref "U1") (pin "7") (pinfunction "NRST_7") (pintype "passive"))
    )
    (net (code "25") (name "/PWM") (class "Default")
      (node (ref "J8") (pin "5") (pinfunction "5_5") (pintype "passive"))
      (node (ref "TP12") (pin "1") (pinfunction "1_1") (pintype "passive"))
      (node (ref "U1") (pin "18") (pinfunction "PB0_18") (pintype "passive"))
    )
    (net (code "26") (name "/RTC_INT") (class "Default")
      (node (ref "J7") (pin "3") (pinfunction "3_3") (pintype "passive"))
      (node (ref "TP17") (pin "1") (pinfunction "1_1") (pintype "passive"))
      (node (ref "U1") (pin "41") (pinfunction "PB5_41") (pintype "passive"))
    )
    (net (code "27") (name "/RTC_SCL") (class "Default")
      (node (ref "J7") (pin "4") (pinfunction "4_4") (pintype "passive"))
      (node (ref "TP18") (pin "1") (pinfunction "1_1") (pintype "passive"))
      (node (ref "U1") (pin "42") (pinfunction "PB6_42") (pintype "passive"))
    )
    (net (code "28") (name "/RTC_SDA") (class "Default")
      (node (ref "J7") (pin "5") (pinfunction "5_5") (pintype "passive"))
      (node (ref "TP19") (pin "1") (pinfunction "1_1") (pintype "passive"))
      (node (ref "U1") (pin "43") (pinfunction "PB7_43") (pintype "passive"))
    )
    (net (code "29") (name "/STATE") (class "Default")
      (node (ref "J4") (pin "6") (pinfunction "6_6") (pintype "passive"))
      (node (ref "TP11") (pin "1") (pinfunction "1_1") (pintype "passive"))
      (node (ref "U1") (pin "33") (pinfunction "PA12_33") (pintype "passive"))
    )
    (net (code "30") (name "/SWCLK") (class "Default")
      (node (ref "J1") (pin "2") (pinfunction "2_2") (pintype "passive"))
      (node (ref "U1") (pin "37") (pinfunction "PA14_37") (pintype "passive"))
    )
    (net (code "31") (name "/SWDIO") (class "Default")
      (node (ref "J1") (pin "4") (pinfunction "4_4") (pintype "passive"))
      (node (ref "U1") (pin "34") (pinfunction "PA13_34") (pintype "passive"))
    )
    (net (code "32") (name "/SWO") (class "Default")
      (node (ref "J1") (pin "6") (pinfunction "6_6") (pintype "passive"))
      (node (ref "U1") (pin "39") (pinfunction "PB3_39") (pintype "passive"))
    )
    (net (code "33") (name "/UART_RX") (class "Default")
      (node (ref "J4") (pin "4") (pinfunction "4_4") (pintype "passive"))
      (node (ref "TP8") (pin "1") (pinfunction "1_1") (pintype "passive"))
      (node (ref "U1") (pin "30") (pinfunction "PA9_30") (pintype "passive"))
    )
    (net (code "34") (name "/UART_TX") (class "Default")
      (node (ref "J4") (pin "5") (pinfunction "5_5") (pintype "passive"))
      (node (ref "TP9") (pin "1") (pinfunction "1_1") (pintype "passive"))
      (node (ref "U1") (pin "31") (pinfunction "PA10_31") (pintype "passive"))
    )
    (net (code "35") (name "GND") (class "Default")
      (node (ref "C1") (pin "1") (pinfunction "1_1") (pintype "passive"))
      (node (ref "C10") (pin "1") (pinfunction "1_1") (pintype "passive"))
      (node (ref "C11") (pin "1") (pinfunction "1_1") (pintype "passive"))
      (node (ref "C12") (pin "1") (pinfunction "1_1") (pintype "passive"))
      (node (ref "C13") (pin "2") (pinfunction "2_2") (pintype "passive"))
      (node (ref "C14") (pin "1") (pinfunction "1_1") (pintype "passive"))
      (node (ref "C15") (pin "2") (pinfunction "2_2") (pintype "passive"))
      (node (ref "C16") (pin "2") (pinfunction "2_2") (pintype "passive"))
      (node (ref "C17") (pin "1") (pinfunction "1_1") (pintype "passive"))
      (node (ref "C18") (pin "1") (pinfunction "1_1") (pintype "passive"))
      (node (ref "C2") (pin "1") (pinfunction "1_1") (pintype "passive"))
      (node (ref "C3") (pin "1") (pinfunction "1_1") (pintype "passive"))
      (node (ref "C4") (pin "1") (pinfunction "1_1") (pintype "passive"))
      (node (ref "C5") (pin "1") (pinfunction "1_1") (pintype "passive"))
      (node (ref "C6") (pin "1") (pinfunction "1_1") (pintype "passive"))
      (node (ref "C7") (pin "1") (pinfunction "1_1") (pintype "passive"))
      (node (ref "C8") (pin "1") (pinfunction "1_1") (pintype "passive"))
      (node (ref "C9") (pin "1") (pinfunction "1_1") (pintype "passive"))
      (node (ref "D1") (pin "1") (pinfunction "1_1") (pintype "passive"))
      (node (ref "J1") (pin "3") (pinfunction "3_3") (pintype "passive"))
      (node (ref "J3") (pin "2") (pinfunction "2_2") (pintype "passive"))
      (node (ref "J4") (pin "3") (pinfunction "3_3") (pintype "passive"))
      (node (ref "J7") (pin "6") (pinfunction "6_6") (pintype "passive"))
      (node (ref "J8") (pin "3") (pinfunction "3_3") (pintype "passive"))
      (node (ref "J8") (pin "4") (pinfunction "4_4") (pintype "passive"))
      (node (ref "Q1") (pin "3") (pinfunction "S_3") (pintype "passive"))
      (node (ref "R12") (pin "1") (pinfunction "1_1") (pintype "passive"))
      (node (ref "R13") (pin "1") (pinfunction "1_1") (pintype "passive"))
      (node (ref "R14") (pin "1") (pinfunction "1_1") (pintype "passive"))
      (node (ref "R15") (pin "1") (pinfunction "1_1") (pintype "passive"))
      (node (ref "R16") (pin "1") (pinfunction "1_1") (pintype "passive"))
      (node (ref "R18") (pin "1") (pinfunction "1_1") (pintype "passive"))
      (node (ref "R24") (pin "1") (pinfunction "1_1") (pintype "passive"))
      (node (ref "R5") (pin "1") (pinfunction "1_1") (pintype "passive"))
      (node (ref "S1") (pin "2") (pinfunction "2_2") (pintype "passive"))
      (node (ref "T1") (pin "2") (pinfunction "E_2") (pintype "passive"))
      (node (ref "TP40") (pin "1") (pinfunction "1_1") (pintype "passive"))
      (node (ref "TP41") (pin "1") (pinfunction "1_1") (pintype "passive"))
      (node (ref "TP44") (pin "1") (pinfunction "1_1") (pintype "passive"))
      (node (ref "TP47") (pin "1") (pinfunction "1_1") (pintype "passive"))
      (node (ref "U1") (pin "23") (pinfunction "VSS_1_23") (pintype "passive"))
      (node (ref "U1") (pin "35") (pinfunction "VSS_2_35") (pintype "passive"))
      (node (ref "U1") (pin "47") (pinfunction "VSS_3_47") (pintype "passive"))
      (node (ref "U1") (pin "8") (pinfunction "VSSA_8") (pintype "passive"))
      (node (ref "U2") (pin "4") (pinfunction "GND_4") (pintype "passive"))
      (node (ref "U3") (pin "1") (pinfunction "GND_1") (pintype "passive"))
      (node (ref "X2") (pin "2") (pinfunction "2_2") (pintype "passive"))
    )
    (net (code "36") (name "Net-(A1-Pad1)") (class "Default")
      (node (ref "A1") (pin "1") (pinfunction "1_1") (pintype "passive"))
      (node (ref "R13") (pin "2") (pinfunction "2_2") (pintype "passive"))
    )
    (net (code "37") (name "Net-(A2-Pad1)") (class "Default")
      (node (ref "A2") (pin "1") (pinfunction "1_1") (pintype "passive"))
      (node (ref "R14") (pin "2") (pinfunction "2_2") (pintype "passive"))
    )
    (net (code "38") (name "Net-(A3-Pad1)") (class "Default")
      (node (ref "A3") (pin "1") (pinfunction "1_1") (pintype "passive"))
      (node (ref "R15") (pin "2") (pinfunction "2_2") (pintype "passive"))
    )
    (net (code "39") (name "Net-(A4-Pad1)") (class "Default")
      (node (ref "A4") (pin "1") (pinfunction "1_1") (pintype "passive"))
      (node (ref "R16") (pin "2") (pinfunction "2_2") (pintype "passive"))
    )
    (net (code "40") (name "Net-(C6-Pad2)") (class "Default")
      (node (ref "C6") (pin "2") (pinfunction "2_2") (pintype "passive"))
      (node (ref "R2") (pin "1") (pinfunction "1_1") (pintype "passive"))
      (node (ref "R3") (pin "1") (pinfunction "1_1") (pintype "passive"))
      (node (ref "S1") (pin "1") (pinfunction "1_1") (pintype "passive"))
    )
    (net (code "41") (name "Net-(C7-Pad2)") (class "Default")
      (node (ref "C7") (pin "2") (pinfunction "2_2") (pintype "passive"))
      (node (ref "R6") (pin "1") (pinfunction "1_1") (pintype "passive"))
      (node (ref "R7") (pin "2") (pinfunction "2_2") (pintype "passive"))
      (node (ref "TP30") (pin "1") (pinfunction "1_1") (pintype "passive"))
      (node (ref "X1") (pin "2") (pinfunction "2_2") (pintype "passive"))
    )
    (net (code "42") (name "Net-(C13-Pad1)") (class "Default")
      (node (ref "C13") (pin "1") (pinfunction "1_1") (pintype "passive"))
      (node (ref "J11") (pin "2") (pinfunction "2_2") (pintype "passive"))
      (node (ref "L1") (pin "1") (pinfunction "1_1") (pintype "passive"))
      (node (ref "R11") (pin "2") (pinfunction "2_2") (pintype "passive"))
      (node (ref "TP42") (pin "1") (pinfunction "1_1") (pintype "passive"))
    )
    (net (code "43") (name "Net-(C17-Pad2)") (class "Default")
      (node (ref "C17") (pin "2") (pinfunction "2_2") (pintype "passive"))
      (node (ref "R17") (pin "1") (pinfunction "1_1") (pintype "passive"))
    )
    (net (code "44") (name "Net-(F1-Pad1)") (class "Default")
      (node (ref "F1") (pin "1") (pinfunction "1_1") (pintype "passive"))
      (node (ref "TP36") (pin "1") (pinfunction "1_1") (pintype "passive"))
      (node (ref "X2") (pin "1") (pinfunction "1_1") (pintype "passive"))
    )
    (net (code "45") (name "Net-(POT1-Pad1)") (class "Default")
      (node (ref "POT1") (pin "1") (pinfunction "1_1") (pintype "passive"))
      (node (ref "R23") (pin "1") (pinfunction "1_1") (pintype "passive"))
    )
    (net (code "46") (name "Net-(POT1-Pad3)") (class "Default")
      (node (ref "POT1") (pin "3") (pinfunction "3_3") (pintype "passive"))
      (node (ref "R24") (pin "2") (pinfunction "2_2") (pintype "passive"))
    )
    (net (code "47") (name "Net-(Q1-D)") (class "Default")
      (node (ref "D2") (pin "1") (pinfunction "1_1") (pintype "passive"))
      (node (ref "L2") (pin "2") (pinfunction "2_2") (pintype "passive"))
      (node (ref "Q1") (pin "2") (pinfunction "D_2") (pintype "passive"))
      (node (ref "R17") (pin "2") (pinfunction "2_2") (pintype "passive"))
      (node (ref "TP45") (pin "1") (pinfunction "1_1") (pintype "passive"))
    )
    (net (code "48") (name "Net-(Q1-G)") (class "Default")
      (node (ref "Q1") (pin "1") (pinfunction "G_1") (pintype "passive"))
      (node (ref "R21") (pin "2") (pinfunction "2_2") (pintype "passive"))
      (node (ref "TP48") (pin "1") (pinfunction "1_1") (pintype "passive"))
    )
    (net (code "49") (name "Net-(R10-Pad2)") (class "Default")
      (node (ref "R10") (pin "2") (pinfunction "2_2") (pintype "passive"))
      (node (ref "R11") (pin "1") (pinfunction "1_1") (pintype "passive"))
    )
    (net (code "50") (name "Net-(T1-B)") (class "Default")
      (node (ref "POT1") (pin "2") (pinfunction "2_2") (pintype "passive"))
      (node (ref "T1") (pin "1") (pinfunction "B_1") (pintype "passive"))
      (node (ref "TP49") (pin "1") (pinfunction "1_1") (pintype "passive"))
    )
    (net (code "51") (name "Net-(T1-C)") (class "Default")
      (node (ref "R20") (pin "1") (pinfunction "1_1") (pintype "passive"))
      (node (ref "T1") (pin "3") (pinfunction "C_3") (pintype "passive"))
      (node (ref "U3") (pin "5") (pinfunction "CTRL_5") (pintype "passive"))
    )
    (net (code "52") (name "Net-(U1-BOOT0)") (class "Default")
      (node (ref "R4") (pin "1") (pinfunction "1_1") (pintype "passive"))
      (node (ref "R5") (pin "2") (pinfunction "2_2") (pintype "passive"))
      (node (ref "TP28") (pin "1") (pinfunction "1_1") (pintype "passive"))
      (node (ref "U1") (pin "44") (pinfunction "BOOT0_44") (pintype "passive"))
    )
    (net (code "53") (name "Net-(U1-PA0-WKUP)") (class "Default")
      (node (ref "C1") (pin "2") (pinfunction "2_2") (pintype "passive"))
      (node (ref "J3") (pin "1") (pinfunction "1_1") (pintype "passive"))
      (node (ref "R1") (pin "1") (pinfunction "1_1") (pintype "passive"))
      (node (ref "TP1") (pin "1") (pinfunction "1_1") (pintype "passive"))
      (node (ref "U1") (pin "10") (pinfunction "PA0-WKUP_10") (pintype "passive"))
    )
    (net (code "54") (name "Net-(U1-PD0-OSC_IN)") (class "Default")
      (node (ref "R6") (pin "2") (pinfunction "2_2") (pintype "passive"))
      (node (ref "U1") (pin "5") (pinfunction "PD0-OSC_IN_5") (pintype "passive"))
    )
    (net (code "55") (name "Net-(U1-PD1-OSC_OUT)") (class "Default")
      (node (ref "C8") (pin "2") (pinfunction "2_2") (pintype "passive"))
      (node (ref "R7") (pin "1") (pinfunction "1_1") (pintype "passive"))
      (node (ref "TP32") (pin "1") (pinfunction "1_1") (pintype "passive"))
      (node (ref "U1") (pin "6") (pinfunction "PD1-OSC_OUT_6") (pintype "passive"))
      (node (ref "X1") (pin "1") (pinfunction "1_1") (pintype "passive"))
    )
    (net (code "56") (name "Net-(U2-CII)") (class "Default")
      (node (ref "R10") (pin "1") (pinfunction "1_1") (pintype "passive"))
      (node (ref "R12") (pin "2") (pinfunction "2_2") (pintype "passive"))
      (node (ref "TP43") (pin "1") (pinfunction "1_1") (pintype "passive"))
      (node (ref "U2") (pin "5") (pinfunction "CII_5") (pintype "passive"))
    )
    (net (code "57") (name "Net-(U2-DC)") (class "Default")
      (node (ref "R8") (pin "2") (pinfunction "2_2") (pintype "passive"))
      (node (ref "R9") (pin "2") (pinfunction "2_2") (pintype "passive"))
      (node (ref "TP35") (pin "1") (pinfunction "1_1") (pintype "passive"))
      (node (ref "U2") (pin "1") (pinfunction "SC_1") (pintype "passive"))
      (node (ref "U2") (pin "7") (pinfunction "ISENSE_7") (pintype "passive"))
      (node (ref "U2") (pin "8") (pinfunction "DC_8") (pintype "passive"))
    )
    (net (code "58") (name "Net-(U2-SE)") (class "Default")
      (node (ref "D1") (pin "2") (pinfunction "2_2") (pintype "passive"))
      (node (ref "L1") (pin "2") (pinfunction "2_2") (pintype "passive"))
      (node (ref "TP38") (pin "1") (pinfunction "1_1") (pintype "passive"))
      (node (ref "U2") (pin "2") (pinfunction "SE_2") (pintype "passive"))
    )
    (net (code "59") (name "Net-(U2-TC)") (class "Default")
      (node (ref "C12") (pin "2") (pinfunction "2_2") (pintype "passive"))
      (node (ref "TP39") (pin "1") (pinfunction "1_1") (pintype "passive"))
      (node (ref "U2") (pin "3") (pinfunction "TC_3") (pintype "passive"))
    )
    (net (code "60") (name "Net-(U3-DIS)") (class "Default")
      (node (ref "R19") (pin "1") (pinfunction "1_1") (pintype "passive"))
      (node (ref "R22") (pin "2") (pinfunction "2_2") (pintype "passive"))
      (node (ref "U3") (pin "7") (pinfunction "DIS_7") (pintype "passive"))
    )
    (net (code "61") (name "Net-(U3-OUT)") (class "Default")
      (node (ref "R21") (pin "1") (pinfunction "1_1") (pintype "passive"))
      (node (ref "U3") (pin "3") (pinfunction "OUT_3") (pintype "passive"))
    )
    (net (code "62") (name "Net-(U3-THR)") (class "Default")
      (node (ref "C18") (pin "2") (pinfunction "2_2") (pintype "passive"))
      (node (ref "R22") (pin "1") (pinfunction "1_1") (pintype "passive"))
      (node (ref "U3") (pin "2") (pinfunction "TRIG_2") (pintype "passive"))
      (node (ref "U3") (pin "6") (pinfunction "THR_6") (pintype "passive"))
    )
    (net (code "63") (name "Net-(U3-VCC)") (class "Default")
      (node (ref "C15") (pin "1") (pinfunction "1_1") (pintype "passive"))
      (node (ref "F2") (pin "2") (pinfunction "2_2") (pintype "passive"))
      (node (ref "L2") (pin "1") (pinfunction "1_1") (pintype "passive"))
      (node (ref "R19") (pin "2") (pinfunction "2_2") (pintype "passive"))
      (node (ref "R20") (pin "2") (pinfunction "2_2") (pintype "passive"))
      (node (ref "TP34") (pin "1") (pinfunction "1_1") (pintype "passive"))
      (node (ref "U3") (pin "4") (pinfunction "~{RST}_4") (pintype "passive"))
      (node (ref "U3") (pin "8") (pinfunction "VCC_8") (pintype "passive"))
    )
    (net (code "64") (name "unconnected-(J8-Pad2)") (class "Default")
      (node (ref "J8") (pin "2") (pinfunction "2_2") (pintype "passive+no_connect"))
    )
    (net (code "65") (name "unconnected-(U1-PA7-Pad17)") (class "Default")
      (node (ref "U1") (pin "17") (pinfunction "PA7_17") (pintype "passive"))
    )
    (net (code "66") (name "unconnected-(U1-PA8-Pad29)") (class "Default")
      (node (ref "U1") (pin "29") (pinfunction "PA8_29") (pintype "passive"))
    )
    (net (code "67") (name "unconnected-(U1-PA15-Pad38)") (class "Default")
      (node (ref "U1") (pin "38") (pinfunction "PA15_38") (pintype "passive"))
    )
    (net (code "68") (name "unconnected-(U1-PB4-Pad40)") (class "Default")
      (node (ref "U1") (pin "40") (pinfunction "PB4_40") (pintype "passive"))
    )
    (net (code "69") (name "unconnected-(U1-PC15-OSC32_OUT-Pad4)") (class "Default")
      (node (ref "U1") (pin "4") (pinfunction "PC15-OSC32_OUT_4") (pintype "passive"))
    )
  )
)
